# iDAC2.net
KiCad netlist of a schematic drawn in Altium Designer
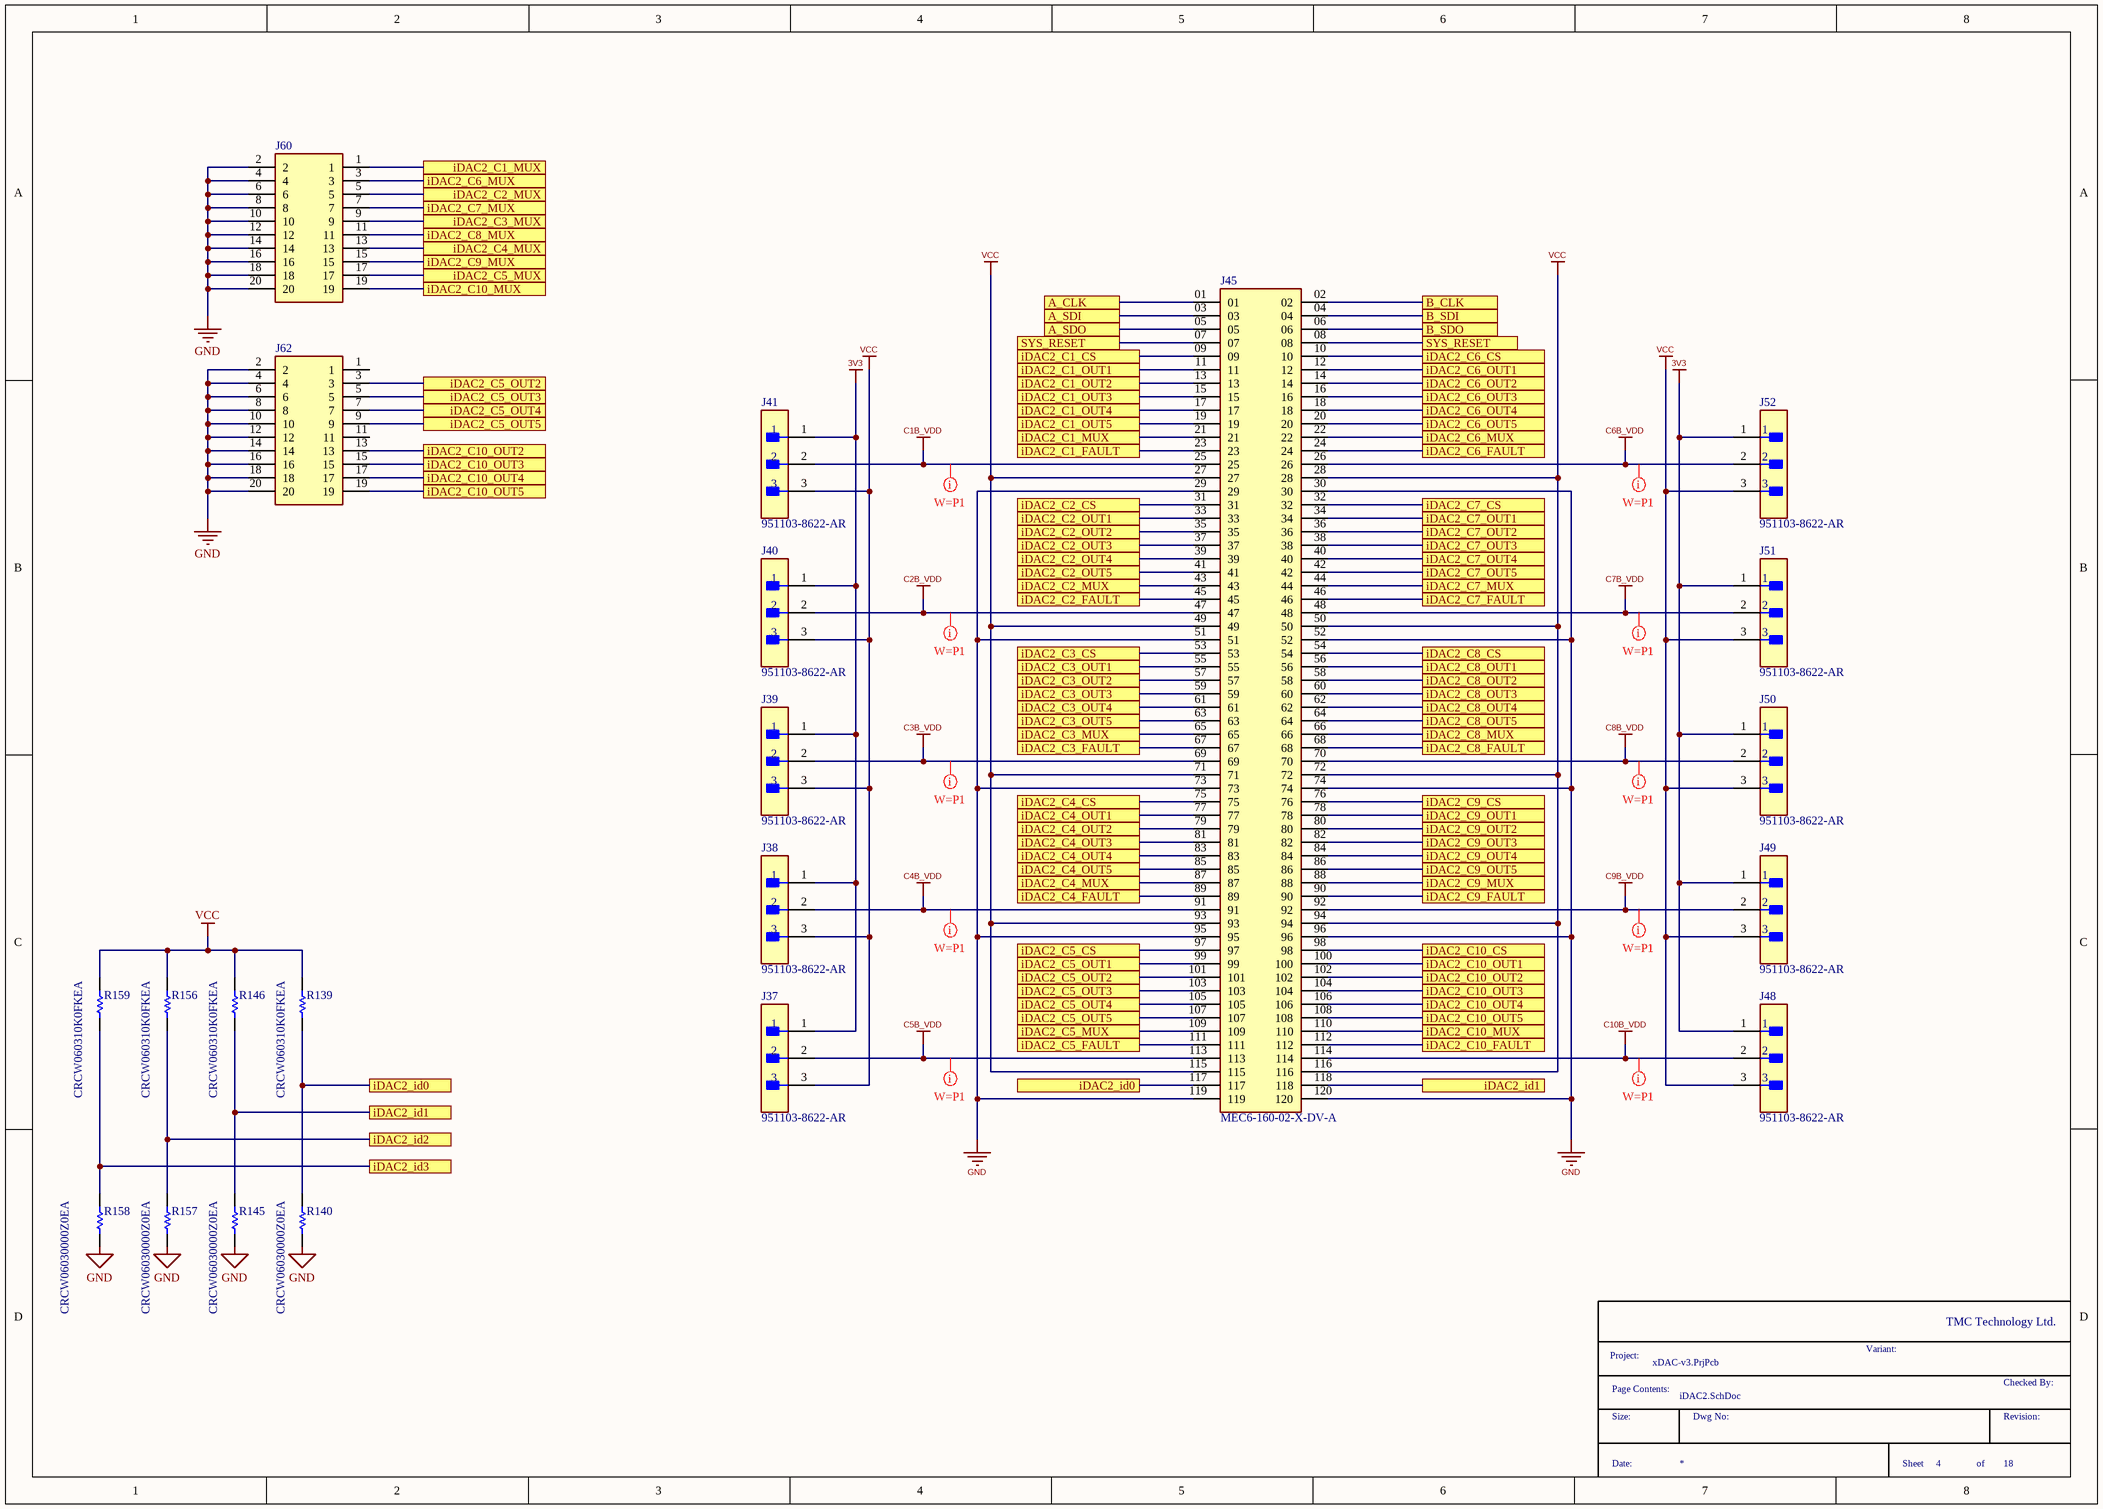
[diagram p0: iDAC2.SchDoc]

(export (version "E")
  (design (tool "Eeschema 10.0.6"))
  (components
    (comp (ref "J37")
      (value "951103-8622-AR")
      (footprint "FP-951103-8622-AR-MFG")
      (description "CONN HEADER VERT 3POS 2MM")
      (fields
        (field (name "OCTOPART") "https://octopart.com/951103-8622-ar-3m-14400669")
        (field (name "MANUFACTURER") "3M")
      )
      (libsource (lib "xDAC_Carrier") (part "CMP-05379-000003-1"))
    )
    (comp (ref "J38")
      (value "951103-8622-AR")
      (footprint "FP-951103-8622-AR-MFG")
      (description "CONN HEADER VERT 3POS 2MM")
      (fields
        (field (name "OCTOPART") "https://octopart.com/951103-8622-ar-3m-14400669")
        (field (name "MANUFACTURER") "3M")
      )
      (libsource (lib "xDAC_Carrier") (part "CMP-05379-000003-1"))
    )
    (comp (ref "J39")
      (value "951103-8622-AR")
      (footprint "FP-951103-8622-AR-MFG")
      (description "CONN HEADER VERT 3POS 2MM")
      (fields
        (field (name "OCTOPART") "https://octopart.com/951103-8622-ar-3m-14400669")
        (field (name "MANUFACTURER") "3M")
      )
      (libsource (lib "xDAC_Carrier") (part "CMP-05379-000003-1"))
    )
    (comp (ref "J40")
      (value "951103-8622-AR")
      (footprint "FP-951103-8622-AR-MFG")
      (description "CONN HEADER VERT 3POS 2MM")
      (fields
        (field (name "OCTOPART") "https://octopart.com/951103-8622-ar-3m-14400669")
        (field (name "MANUFACTURER") "3M")
      )
      (libsource (lib "xDAC_Carrier") (part "CMP-05379-000003-1"))
    )
    (comp (ref "J41")
      (value "951103-8622-AR")
      (footprint "FP-951103-8622-AR-MFG")
      (description "CONN HEADER VERT 3POS 2MM")
      (fields
        (field (name "OCTOPART") "https://octopart.com/951103-8622-ar-3m-14400669")
        (field (name "MANUFACTURER") "3M")
      )
      (libsource (lib "xDAC_Carrier") (part "CMP-05379-000003-1"))
    )
    (comp (ref "J45")
      (value "MEC6-160-02-X-DV-A")
      (footprint "SAMTEC_MEC6-160-02-X-DV-A")
      (fields (field (name "MF") "Samtec Inc."))
      (libsource (lib "xDAC_Carrier") (part "MEC6-160-02-X-DV-A"))
    )
    (comp (ref "J48")
      (value "951103-8622-AR")
      (footprint "FP-951103-8622-AR-MFG")
      (description "CONN HEADER VERT 3POS 2MM")
      (fields
        (field (name "OCTOPART") "https://octopart.com/951103-8622-ar-3m-14400669")
        (field (name "MANUFACTURER") "3M")
      )
      (libsource (lib "") (part "CMP-05379-000003-1_1"))
    )
    (comp (ref "J49")
      (value "951103-8622-AR")
      (footprint "FP-951103-8622-AR-MFG")
      (description "CONN HEADER VERT 3POS 2MM")
      (fields
        (field (name "OCTOPART") "https://octopart.com/951103-8622-ar-3m-14400669")
        (field (name "MANUFACTURER") "3M")
      )
      (libsource (lib "") (part "CMP-05379-000003-1_1"))
    )
    (comp (ref "J50")
      (value "951103-8622-AR")
      (footprint "FP-951103-8622-AR-MFG")
      (description "CONN HEADER VERT 3POS 2MM")
      (fields
        (field (name "OCTOPART") "https://octopart.com/951103-8622-ar-3m-14400669")
        (field (name "MANUFACTURER") "3M")
      )
      (libsource (lib "") (part "CMP-05379-000003-1_1"))
    )
    (comp (ref "J51")
      (value "951103-8622-AR")
      (footprint "FP-951103-8622-AR-MFG")
      (description "CONN HEADER VERT 3POS 2MM")
      (fields
        (field (name "OCTOPART") "https://octopart.com/951103-8622-ar-3m-14400669")
        (field (name "MANUFACTURER") "3M")
      )
      (libsource (lib "") (part "CMP-05379-000003-1_1"))
    )
    (comp (ref "J52")
      (value "951103-8622-AR")
      (footprint "FP-951103-8622-AR-MFG")
      (description "CONN HEADER VERT 3POS 2MM")
      (fields
        (field (name "OCTOPART") "https://octopart.com/951103-8622-ar-3m-14400669")
        (field (name "MANUFACTURER") "3M")
      )
      (libsource (lib "") (part "CMP-05379-000003-1_1"))
    )
    (comp (ref "J60")
      (value "~")
      (footprint "HDRV20W40P127_2X10_1270X340X550P")
      (description "Connector")
      (fields (field (name "MANUFACTURER_PART_NUMBER") "20021111-00020T4LF"))
      (libsource (lib "xDAC_Carrier") (part "20021111-00020T4LF"))
    )
    (comp (ref "J62")
      (value "~")
      (footprint "HDRV20W40P127_2X10_1270X340X550P")
      (description "Connector")
      (fields (field (name "MANUFACTURER_PART_NUMBER") "20021111-00020T4LF"))
      (libsource (lib "xDAC_Carrier") (part "20021111-00020T4LF"))
    )
    (comp (ref "R139")
      (value "CRCW060310K0FKEA")
      (footprint "RESC1609X50X30NL8T20")
      (description "Chip Resistor, 10 KOhm, +/- 1%, 100 mW, -55 to 155 degC, 0603 (1608 Metric), RoHS, Tape and Reel")
      (fields (field (name "MANUFACTURER") "Vishay Semiconductor"))
      (libsource (lib "Altium Content Vault") (part "RES-2"))
    )
    (comp (ref "R140")
      (value "CRCW06030000Z0EA")
      (footprint "RESC1609X50X30NL8T20")
      (description "Chip Resistor, 0 Ohm, Jumper, 100 mW, -55 to 155 degC, 0603 (1608 Metric), RoHS, Tape and Reel")
      (fields (field (name "MANUFACTURER") "Vishay Semiconductor"))
      (libsource (lib "Altium Content Vault") (part "RES-2"))
    )
    (comp (ref "R145")
      (value "CRCW06030000Z0EA")
      (footprint "RESC1609X50X30NL8T20")
      (description "Chip Resistor, 0 Ohm, Jumper, 100 mW, -55 to 155 degC, 0603 (1608 Metric), RoHS, Tape and Reel")
      (fields (field (name "MANUFACTURER") "Vishay Semiconductor"))
      (libsource (lib "Altium Content Vault") (part "RES-2"))
    )
    (comp (ref "R146")
      (value "CRCW060310K0FKEA")
      (footprint "RESC1609X50X30NL8T20")
      (description "Chip Resistor, 10 KOhm, +/- 1%, 100 mW, -55 to 155 degC, 0603 (1608 Metric), RoHS, Tape and Reel")
      (fields (field (name "MANUFACTURER") "Vishay Semiconductor"))
      (libsource (lib "Altium Content Vault") (part "RES-2"))
    )
    (comp (ref "R156")
      (value "CRCW060310K0FKEA")
      (footprint "RESC1609X50X30NL8T20")
      (description "Chip Resistor, 10 KOhm, +/- 1%, 100 mW, -55 to 155 degC, 0603 (1608 Metric), RoHS, Tape and Reel")
      (fields (field (name "MANUFACTURER") "Vishay Semiconductor"))
      (libsource (lib "Altium Content Vault") (part "RES-2"))
    )
    (comp (ref "R157")
      (value "CRCW06030000Z0EA")
      (footprint "RESC1609X50X30NL8T20")
      (description "Chip Resistor, 0 Ohm, Jumper, 100 mW, -55 to 155 degC, 0603 (1608 Metric), RoHS, Tape and Reel")
      (fields (field (name "MANUFACTURER") "Vishay Semiconductor"))
      (libsource (lib "Altium Content Vault") (part "RES-2"))
    )
    (comp (ref "R158")
      (value "CRCW06030000Z0EA")
      (footprint "RESC1609X50X30NL8T20")
      (description "Chip Resistor, 0 Ohm, Jumper, 100 mW, -55 to 155 degC, 0603 (1608 Metric), RoHS, Tape and Reel")
      (fields (field (name "MANUFACTURER") "Vishay Semiconductor"))
      (libsource (lib "Altium Content Vault") (part "RES-2"))
    )
    (comp (ref "R159")
      (value "CRCW060310K0FKEA")
      (footprint "RESC1609X50X30NL8T20")
      (description "Chip Resistor, 10 KOhm, +/- 1%, 100 mW, -55 to 155 degC, 0603 (1608 Metric), RoHS, Tape and Reel")
      (fields (field (name "MANUFACTURER") "Vishay Semiconductor"))
      (libsource (lib "Altium Content Vault") (part "RES-2"))
    )
  )
  (nets
    (net (code "1") (name "/A_CLK") (class "Default")
      (node (ref "J45") (pin "01") (pinfunction "01_01") (pintype "passive"))
    )
    (net (code "2") (name "/A_SDI") (class "Default")
      (node (ref "J45") (pin "03") (pinfunction "03_03") (pintype "passive"))
    )
    (net (code "3") (name "/A_SDO") (class "Default")
      (node (ref "J45") (pin "05") (pinfunction "05_05") (pintype "passive"))
    )
    (net (code "4") (name "/B_CLK") (class "Default")
      (node (ref "J45") (pin "02") (pinfunction "02_02") (pintype "passive"))
    )
    (net (code "5") (name "/B_SDI") (class "Default")
      (node (ref "J45") (pin "04") (pinfunction "04_04") (pintype "passive"))
    )
    (net (code "6") (name "/B_SDO") (class "Default")
      (node (ref "J45") (pin "06") (pinfunction "06_06") (pintype "passive"))
    )
    (net (code "7") (name "/SYS_RESET") (class "Default")
      (node (ref "J45") (pin "07") (pinfunction "07_07") (pintype "passive"))
      (node (ref "J45") (pin "08") (pinfunction "08_08") (pintype "passive"))
    )
    (net (code "8") (name "/iDAC2_C1_CS") (class "Default")
      (node (ref "J45") (pin "09") (pinfunction "09_09") (pintype "passive"))
    )
    (net (code "9") (name "/iDAC2_C1_FAULT") (class "Default")
      (node (ref "J45") (pin "23") (pinfunction "23_23") (pintype "passive"))
    )
    (net (code "10") (name "/iDAC2_C1_MUX") (class "Default")
      (node (ref "J45") (pin "21") (pinfunction "21_21") (pintype "passive"))
      (node (ref "J60") (pin "1") (pinfunction "1_1") (pintype "passive"))
    )
    (net (code "11") (name "/iDAC2_C1_OUT1") (class "Default")
      (node (ref "J45") (pin "11") (pinfunction "11_11") (pintype "passive"))
    )
    (net (code "12") (name "/iDAC2_C1_OUT2") (class "Default")
      (node (ref "J45") (pin "13") (pinfunction "13_13") (pintype "passive"))
    )
    (net (code "13") (name "/iDAC2_C1_OUT3") (class "Default")
      (node (ref "J45") (pin "15") (pinfunction "15_15") (pintype "passive"))
    )
    (net (code "14") (name "/iDAC2_C1_OUT4") (class "Default")
      (node (ref "J45") (pin "17") (pinfunction "17_17") (pintype "passive"))
    )
    (net (code "15") (name "/iDAC2_C1_OUT5") (class "Default")
      (node (ref "J45") (pin "19") (pinfunction "19_19") (pintype "passive"))
    )
    (net (code "16") (name "/iDAC2_C2_CS") (class "Default")
      (node (ref "J45") (pin "31") (pinfunction "31_31") (pintype "passive"))
    )
    (net (code "17") (name "/iDAC2_C2_FAULT") (class "Default")
      (node (ref "J45") (pin "45") (pinfunction "45_45") (pintype "passive"))
    )
    (net (code "18") (name "/iDAC2_C2_MUX") (class "Default")
      (node (ref "J45") (pin "43") (pinfunction "43_43") (pintype "passive"))
      (node (ref "J60") (pin "5") (pinfunction "5_5") (pintype "passive"))
    )
    (net (code "19") (name "/iDAC2_C2_OUT1") (class "Default")
      (node (ref "J45") (pin "33") (pinfunction "33_33") (pintype "passive"))
    )
    (net (code "20") (name "/iDAC2_C2_OUT2") (class "Default")
      (node (ref "J45") (pin "35") (pinfunction "35_35") (pintype "passive"))
    )
    (net (code "21") (name "/iDAC2_C2_OUT3") (class "Default")
      (node (ref "J45") (pin "37") (pinfunction "37_37") (pintype "passive"))
    )
    (net (code "22") (name "/iDAC2_C2_OUT4") (class "Default")
      (node (ref "J45") (pin "39") (pinfunction "39_39") (pintype "passive"))
    )
    (net (code "23") (name "/iDAC2_C2_OUT5") (class "Default")
      (node (ref "J45") (pin "41") (pinfunction "41_41") (pintype "passive"))
    )
    (net (code "24") (name "/iDAC2_C3_CS") (class "Default")
      (node (ref "J45") (pin "53") (pinfunction "53_53") (pintype "passive"))
    )
    (net (code "25") (name "/iDAC2_C3_FAULT") (class "Default")
      (node (ref "J45") (pin "67") (pinfunction "67_67") (pintype "passive"))
    )
    (net (code "26") (name "/iDAC2_C3_MUX") (class "Default")
      (node (ref "J45") (pin "65") (pinfunction "65_65") (pintype "passive"))
      (node (ref "J60") (pin "9") (pinfunction "9_9") (pintype "passive"))
    )
    (net (code "27") (name "/iDAC2_C3_OUT1") (class "Default")
      (node (ref "J45") (pin "55") (pinfunction "55_55") (pintype "passive"))
    )
    (net (code "28") (name "/iDAC2_C3_OUT2") (class "Default")
      (node (ref "J45") (pin "57") (pinfunction "57_57") (pintype "passive"))
    )
    (net (code "29") (name "/iDAC2_C3_OUT3") (class "Default")
      (node (ref "J45") (pin "59") (pinfunction "59_59") (pintype "passive"))
    )
    (net (code "30") (name "/iDAC2_C3_OUT4") (class "Default")
      (node (ref "J45") (pin "61") (pinfunction "61_61") (pintype "passive"))
    )
    (net (code "31") (name "/iDAC2_C3_OUT5") (class "Default")
      (node (ref "J45") (pin "63") (pinfunction "63_63") (pintype "passive"))
    )
    (net (code "32") (name "/iDAC2_C4_CS") (class "Default")
      (node (ref "J45") (pin "75") (pinfunction "75_75") (pintype "passive"))
    )
    (net (code "33") (name "/iDAC2_C4_FAULT") (class "Default")
      (node (ref "J45") (pin "89") (pinfunction "89_89") (pintype "passive"))
    )
    (net (code "34") (name "/iDAC2_C4_MUX") (class "Default")
      (node (ref "J45") (pin "87") (pinfunction "87_87") (pintype "passive"))
      (node (ref "J60") (pin "13") (pinfunction "13_13") (pintype "passive"))
    )
    (net (code "35") (name "/iDAC2_C4_OUT1") (class "Default")
      (node (ref "J45") (pin "77") (pinfunction "77_77") (pintype "passive"))
    )
    (net (code "36") (name "/iDAC2_C4_OUT2") (class "Default")
      (node (ref "J45") (pin "79") (pinfunction "79_79") (pintype "passive"))
    )
    (net (code "37") (name "/iDAC2_C4_OUT3") (class "Default")
      (node (ref "J45") (pin "81") (pinfunction "81_81") (pintype "passive"))
    )
    (net (code "38") (name "/iDAC2_C4_OUT4") (class "Default")
      (node (ref "J45") (pin "83") (pinfunction "83_83") (pintype "passive"))
    )
    (net (code "39") (name "/iDAC2_C4_OUT5") (class "Default")
      (node (ref "J45") (pin "85") (pinfunction "85_85") (pintype "passive"))
    )
    (net (code "40") (name "/iDAC2_C5_CS") (class "Default")
      (node (ref "J45") (pin "97") (pinfunction "97_97") (pintype "passive"))
    )
    (net (code "41") (name "/iDAC2_C5_FAULT") (class "Default")
      (node (ref "J45") (pin "111") (pinfunction "111_111") (pintype "passive"))
    )
    (net (code "42") (name "/iDAC2_C5_MUX") (class "Default")
      (node (ref "J45") (pin "109") (pinfunction "109_109") (pintype "passive"))
      (node (ref "J60") (pin "17") (pinfunction "17_17") (pintype "passive"))
    )
    (net (code "43") (name "/iDAC2_C5_OUT1") (class "Default")
      (node (ref "J45") (pin "99") (pinfunction "99_99") (pintype "passive"))
    )
    (net (code "44") (name "/iDAC2_C5_OUT2") (class "Default")
      (node (ref "J45") (pin "101") (pinfunction "101_101") (pintype "passive"))
      (node (ref "J62") (pin "3") (pinfunction "3_3") (pintype "passive"))
    )
    (net (code "45") (name "/iDAC2_C5_OUT3") (class "Default")
      (node (ref "J45") (pin "103") (pinfunction "103_103") (pintype "passive"))
      (node (ref "J62") (pin "5") (pinfunction "5_5") (pintype "passive"))
    )
    (net (code "46") (name "/iDAC2_C5_OUT4") (class "Default")
      (node (ref "J45") (pin "105") (pinfunction "105_105") (pintype "passive"))
      (node (ref "J62") (pin "7") (pinfunction "7_7") (pintype "passive"))
    )
    (net (code "47") (name "/iDAC2_C5_OUT5") (class "Default")
      (node (ref "J45") (pin "107") (pinfunction "107_107") (pintype "passive"))
      (node (ref "J62") (pin "9") (pinfunction "9_9") (pintype "passive"))
    )
    (net (code "48") (name "/iDAC2_C6_CS") (class "Default")
      (node (ref "J45") (pin "10") (pinfunction "10_10") (pintype "passive"))
    )
    (net (code "49") (name "/iDAC2_C6_FAULT") (class "Default")
      (node (ref "J45") (pin "24") (pinfunction "24_24") (pintype "passive"))
    )
    (net (code "50") (name "/iDAC2_C6_MUX") (class "Default")
      (node (ref "J45") (pin "22") (pinfunction "22_22") (pintype "passive"))
      (node (ref "J60") (pin "3") (pinfunction "3_3") (pintype "passive"))
    )
    (net (code "51") (name "/iDAC2_C6_OUT1") (class "Default")
      (node (ref "J45") (pin "12") (pinfunction "12_12") (pintype "passive"))
    )
    (net (code "52") (name "/iDAC2_C6_OUT2") (class "Default")
      (node (ref "J45") (pin "14") (pinfunction "14_14") (pintype "passive"))
    )
    (net (code "53") (name "/iDAC2_C6_OUT3") (class "Default")
      (node (ref "J45") (pin "16") (pinfunction "16_16") (pintype "passive"))
    )
    (net (code "54") (name "/iDAC2_C6_OUT4") (class "Default")
      (node (ref "J45") (pin "18") (pinfunction "18_18") (pintype "passive"))
    )
    (net (code "55") (name "/iDAC2_C6_OUT5") (class "Default")
      (node (ref "J45") (pin "20") (pinfunction "20_20") (pintype "passive"))
    )
    (net (code "56") (name "/iDAC2_C7_CS") (class "Default")
      (node (ref "J45") (pin "32") (pinfunction "32_32") (pintype "passive"))
    )
    (net (code "57") (name "/iDAC2_C7_FAULT") (class "Default")
      (node (ref "J45") (pin "46") (pinfunction "46_46") (pintype "passive"))
    )
    (net (code "58") (name "/iDAC2_C7_MUX") (class "Default")
      (node (ref "J45") (pin "44") (pinfunction "44_44") (pintype "passive"))
      (node (ref "J60") (pin "7") (pinfunction "7_7") (pintype "passive"))
    )
    (net (code "59") (name "/iDAC2_C7_OUT1") (class "Default")
      (node (ref "J45") (pin "34") (pinfunction "34_34") (pintype "passive"))
    )
    (net (code "60") (name "/iDAC2_C7_OUT2") (class "Default")
      (node (ref "J45") (pin "36") (pinfunction "36_36") (pintype "passive"))
    )
    (net (code "61") (name "/iDAC2_C7_OUT3") (class "Default")
      (node (ref "J45") (pin "38") (pinfunction "38_38") (pintype "passive"))
    )
    (net (code "62") (name "/iDAC2_C7_OUT4") (class "Default")
      (node (ref "J45") (pin "40") (pinfunction "40_40") (pintype "passive"))
    )
    (net (code "63") (name "/iDAC2_C7_OUT5") (class "Default")
      (node (ref "J45") (pin "42") (pinfunction "42_42") (pintype "passive"))
    )
    (net (code "64") (name "/iDAC2_C8_CS") (class "Default")
      (node (ref "J45") (pin "54") (pinfunction "54_54") (pintype "passive"))
    )
    (net (code "65") (name "/iDAC2_C8_FAULT") (class "Default")
      (node (ref "J45") (pin "68") (pinfunction "68_68") (pintype "passive"))
    )
    (net (code "66") (name "/iDAC2_C8_MUX") (class "Default")
      (node (ref "J45") (pin "66") (pinfunction "66_66") (pintype "passive"))
      (node (ref "J60") (pin "11") (pinfunction "11_11") (pintype "passive"))
    )
    (net (code "67") (name "/iDAC2_C8_OUT1") (class "Default")
      (node (ref "J45") (pin "56") (pinfunction "56_56") (pintype "passive"))
    )
    (net (code "68") (name "/iDAC2_C8_OUT2") (class "Default")
      (node (ref "J45") (pin "58") (pinfunction "58_58") (pintype "passive"))
    )
    (net (code "69") (name "/iDAC2_C8_OUT3") (class "Default")
      (node (ref "J45") (pin "60") (pinfunction "60_60") (pintype "passive"))
    )
    (net (code "70") (name "/iDAC2_C8_OUT4") (class "Default")
      (node (ref "J45") (pin "62") (pinfunction "62_62") (pintype "passive"))
    )
    (net (code "71") (name "/iDAC2_C8_OUT5") (class "Default")
      (node (ref "J45") (pin "64") (pinfunction "64_64") (pintype "passive"))
    )
    (net (code "72") (name "/iDAC2_C9_CS") (class "Default")
      (node (ref "J45") (pin "76") (pinfunction "76_76") (pintype "passive"))
    )
    (net (code "73") (name "/iDAC2_C9_FAULT") (class "Default")
      (node (ref "J45") (pin "90") (pinfunction "90_90") (pintype "passive"))
    )
    (net (code "74") (name "/iDAC2_C9_MUX") (class "Default")
      (node (ref "J45") (pin "88") (pinfunction "88_88") (pintype "passive"))
      (node (ref "J60") (pin "15") (pinfunction "15_15") (pintype "passive"))
    )
    (net (code "75") (name "/iDAC2_C9_OUT1") (class "Default")
      (node (ref "J45") (pin "78") (pinfunction "78_78") (pintype "passive"))
    )
    (net (code "76") (name "/iDAC2_C9_OUT2") (class "Default")
      (node (ref "J45") (pin "80") (pinfunction "80_80") (pintype "passive"))
    )
    (net (code "77") (name "/iDAC2_C9_OUT3") (class "Default")
      (node (ref "J45") (pin "82") (pinfunction "82_82") (pintype "passive"))
    )
    (net (code "78") (name "/iDAC2_C9_OUT4") (class "Default")
      (node (ref "J45") (pin "84") (pinfunction "84_84") (pintype "passive"))
    )
    (net (code "79") (name "/iDAC2_C9_OUT5") (class "Default")
      (node (ref "J45") (pin "86") (pinfunction "86_86") (pintype "passive"))
    )
    (net (code "80") (name "/iDAC2_C10_CS") (class "Default")
      (node (ref "J45") (pin "98") (pinfunction "98_98") (pintype "passive"))
    )
    (net (code "81") (name "/iDAC2_C10_FAULT") (class "Default")
      (node (ref "J45") (pin "112") (pinfunction "112_112") (pintype "passive"))
    )
    (net (code "82") (name "/iDAC2_C10_MUX") (class "Default")
      (node (ref "J45") (pin "110") (pinfunction "110_110") (pintype "passive"))
      (node (ref "J60") (pin "19") (pinfunction "19_19") (pintype "passive"))
    )
    (net (code "83") (name "/iDAC2_C10_OUT1") (class "Default")
      (node (ref "J45") (pin "100") (pinfunction "100_100") (pintype "passive"))
    )
    (net (code "84") (name "/iDAC2_C10_OUT2") (class "Default")
      (node (ref "J45") (pin "102") (pinfunction "102_102") (pintype "passive"))
      (node (ref "J62") (pin "13") (pinfunction "13_13") (pintype "passive"))
    )
    (net (code "85") (name "/iDAC2_C10_OUT3") (class "Default")
      (node (ref "J45") (pin "104") (pinfunction "104_104") (pintype "passive"))
      (node (ref "J62") (pin "15") (pinfunction "15_15") (pintype "passive"))
    )
    (net (code "86") (name "/iDAC2_C10_OUT4") (class "Default")
      (node (ref "J45") (pin "106") (pinfunction "106_106") (pintype "passive"))
      (node (ref "J62") (pin "17") (pinfunction "17_17") (pintype "passive"))
    )
    (net (code "87") (name "/iDAC2_C10_OUT5") (class "Default")
      (node (ref "J45") (pin "108") (pinfunction "108_108") (pintype "passive"))
      (node (ref "J62") (pin "19") (pinfunction "19_19") (pintype "passive"))
    )
    (net (code "88") (name "/iDAC2_id0") (class "Default")
      (node (ref "J45") (pin "117") (pinfunction "117_117") (pintype "passive"))
      (node (ref "R139") (pin "1") (pinfunction "1_1") (pintype "passive"))
      (node (ref "R140") (pin "2") (pinfunction "2_2") (pintype "passive"))
    )
    (net (code "89") (name "/iDAC2_id1") (class "Default")
      (node (ref "J45") (pin "118") (pinfunction "118_118") (pintype "passive"))
      (node (ref "R145") (pin "2") (pinfunction "2_2") (pintype "passive"))
      (node (ref "R146") (pin "1") (pinfunction "1_1") (pintype "passive"))
    )
    (net (code "90") (name "/iDAC2_id2") (class "Default")
      (node (ref "R156") (pin "1") (pinfunction "1_1") (pintype "passive"))
      (node (ref "R157") (pin "2") (pinfunction "2_2") (pintype "passive"))
    )
    (net (code "91") (name "/iDAC2_id3") (class "Default")
      (node (ref "R158") (pin "2") (pinfunction "2_2") (pintype "passive"))
      (node (ref "R159") (pin "1") (pinfunction "1_1") (pintype "passive"))
    )
    (net (code "92") (name "3V3") (class "Default")
      (node (ref "J37") (pin "1") (pinfunction "1_1") (pintype "passive"))
      (node (ref "J38") (pin "1") (pinfunction "1_1") (pintype "passive"))
      (node (ref "J39") (pin "1") (pinfunction "1_1") (pintype "passive"))
      (node (ref "J40") (pin "1") (pinfunction "1_1") (pintype "passive"))
      (node (ref "J41") (pin "1") (pinfunction "1_1") (pintype "passive"))
      (node (ref "J48") (pin "1") (pinfunction "1_1") (pintype "passive"))
      (node (ref "J49") (pin "1") (pinfunction "1_1") (pintype "passive"))
      (node (ref "J50") (pin "1") (pinfunction "1_1") (pintype "passive"))
      (node (ref "J51") (pin "1") (pinfunction "1_1") (pintype "passive"))
      (node (ref "J52") (pin "1") (pinfunction "1_1") (pintype "passive"))
    )
    (net (code "93") (name "C1B_VDD") (class "Default")
      (node (ref "J41") (pin "2") (pinfunction "2_2") (pintype "passive"))
      (node (ref "J45") (pin "25") (pinfunction "25_25") (pintype "passive"))
    )
    (net (code "94") (name "C2B_VDD") (class "Default")
      (node (ref "J40") (pin "2") (pinfunction "2_2") (pintype "passive"))
      (node (ref "J45") (pin "47") (pinfunction "47_47") (pintype "passive"))
    )
    (net (code "95") (name "C3B_VDD") (class "Default")
      (node (ref "J39") (pin "2") (pinfunction "2_2") (pintype "passive"))
      (node (ref "J45") (pin "69") (pinfunction "69_69") (pintype "passive"))
    )
    (net (code "96") (name "C4B_VDD") (class "Default")
      (node (ref "J38") (pin "2") (pinfunction "2_2") (pintype "passive"))
      (node (ref "J45") (pin "91") (pinfunction "91_91") (pintype "passive"))
    )
    (net (code "97") (name "C5B_VDD") (class "Default")
      (node (ref "J37") (pin "2") (pinfunction "2_2") (pintype "passive"))
      (node (ref "J45") (pin "113") (pinfunction "113_113") (pintype "passive"))
    )
    (net (code "98") (name "C6B_VDD") (class "Default")
      (node (ref "J45") (pin "26") (pinfunction "26_26") (pintype "passive"))
      (node (ref "J52") (pin "2") (pinfunction "2_2") (pintype "passive"))
    )
    (net (code "99") (name "C7B_VDD") (class "Default")
      (node (ref "J45") (pin "48") (pinfunction "48_48") (pintype "passive"))
      (node (ref "J51") (pin "2") (pinfunction "2_2") (pintype "passive"))
    )
    (net (code "100") (name "C8B_VDD") (class "Default")
      (node (ref "J45") (pin "70") (pinfunction "70_70") (pintype "passive"))
      (node (ref "J50") (pin "2") (pinfunction "2_2") (pintype "passive"))
    )
    (net (code "101") (name "C9B_VDD") (class "Default")
      (node (ref "J45") (pin "92") (pinfunction "92_92") (pintype "passive"))
      (node (ref "J49") (pin "2") (pinfunction "2_2") (pintype "passive"))
    )
    (net (code "102") (name "C10B_VDD") (class "Default")
      (node (ref "J45") (pin "114") (pinfunction "114_114") (pintype "passive"))
      (node (ref "J48") (pin "2") (pinfunction "2_2") (pintype "passive"))
    )
    (net (code "103") (name "GND") (class "Default")
      (node (ref "J45") (pin "119") (pinfunction "119_119") (pintype "passive"))
      (node (ref "J45") (pin "120") (pinfunction "120_120") (pintype "passive"))
      (node (ref "J45") (pin "29") (pinfunction "29_29") (pintype "passive"))
      (node (ref "J45") (pin "30") (pinfunction "30_30") (pintype "passive"))
      (node (ref "J45") (pin "51") (pinfunction "51_51") (pintype "passive"))
      (node (ref "J45") (pin "52") (pinfunction "52_52") (pintype "passive"))
      (node (ref "J45") (pin "73") (pinfunction "73_73") (pintype "passive"))
      (node (ref "J45") (pin "74") (pinfunction "74_74") (pintype "passive"))
      (node (ref "J45") (pin "95") (pinfunction "95_95") (pintype "passive"))
      (node (ref "J45") (pin "96") (pinfunction "96_96") (pintype "passive"))
      (node (ref "J60") (pin "10") (pinfunction "10_10") (pintype "passive"))
      (node (ref "J60") (pin "12") (pinfunction "12_12") (pintype "passive"))
      (node (ref "J60") (pin "14") (pinfunction "14_14") (pintype "passive"))
      (node (ref "J60") (pin "16") (pinfunction "16_16") (pintype "passive"))
      (node (ref "J60") (pin "18") (pinfunction "18_18") (pintype "passive"))
      (node (ref "J60") (pin "2") (pinfunction "2_2") (pintype "passive"))
      (node (ref "J60") (pin "20") (pinfunction "20_20") (pintype "passive"))
      (node (ref "J60") (pin "4") (pinfunction "4_4") (pintype "passive"))
      (node (ref "J60") (pin "6") (pinfunction "6_6") (pintype "passive"))
      (node (ref "J60") (pin "8") (pinfunction "8_8") (pintype "passive"))
      (node (ref "J62") (pin "10") (pinfunction "10_10") (pintype "passive"))
      (node (ref "J62") (pin "12") (pinfunction "12_12") (pintype "passive"))
      (node (ref "J62") (pin "14") (pinfunction "14_14") (pintype "passive"))
      (node (ref "J62") (pin "16") (pinfunction "16_16") (pintype "passive"))
      (node (ref "J62") (pin "18") (pinfunction "18_18") (pintype "passive"))
      (node (ref "J62") (pin "2") (pinfunction "2_2") (pintype "passive"))
      (node (ref "J62") (pin "20") (pinfunction "20_20") (pintype "passive"))
      (node (ref "J62") (pin "4") (pinfunction "4_4") (pintype "passive"))
      (node (ref "J62") (pin "6") (pinfunction "6_6") (pintype "passive"))
      (node (ref "J62") (pin "8") (pinfunction "8_8") (pintype "passive"))
      (node (ref "R140") (pin "1") (pinfunction "1_1") (pintype "passive"))
      (node (ref "R145") (pin "1") (pinfunction "1_1") (pintype "passive"))
      (node (ref "R157") (pin "1") (pinfunction "1_1") (pintype "passive"))
      (node (ref "R158") (pin "1") (pinfunction "1_1") (pintype "passive"))
    )
    (net (code "104") (name "VCC") (class "Default")
      (node (ref "J37") (pin "3") (pinfunction "3_3") (pintype "passive"))
      (node (ref "J38") (pin "3") (pinfunction "3_3") (pintype "passive"))
      (node (ref "J39") (pin "3") (pinfunction "3_3") (pintype "passive"))
      (node (ref "J40") (pin "3") (pinfunction "3_3") (pintype "passive"))
      (node (ref "J41") (pin "3") (pinfunction "3_3") (pintype "passive"))
      (node (ref "J45") (pin "115") (pinfunction "115_115") (pintype "passive"))
      (node (ref "J45") (pin "116") (pinfunction "116_116") (pintype "passive"))
      (node (ref "J45") (pin "27") (pinfunction "27_27") (pintype "passive"))
      (node (ref "J45") (pin "28") (pinfunction "28_28") (pintype "passive"))
      (node (ref "J45") (pin "49") (pinfunction "49_49") (pintype "passive"))
      (node (ref "J45") (pin "50") (pinfunction "50_50") (pintype "passive"))
      (node (ref "J45") (pin "71") (pinfunction "71_71") (pintype "passive"))
      (node (ref "J45") (pin "72") (pinfunction "72_72") (pintype "passive"))
      (node (ref "J45") (pin "93") (pinfunction "93_93") (pintype "passive"))
      (node (ref "J45") (pin "94") (pinfunction "94_94") (pintype "passive"))
      (node (ref "J48") (pin "3") (pinfunction "3_3") (pintype "passive"))
      (node (ref "J49") (pin "3") (pinfunction "3_3") (pintype "passive"))
      (node (ref "J50") (pin "3") (pinfunction "3_3") (pintype "passive"))
      (node (ref "J51") (pin "3") (pinfunction "3_3") (pintype "passive"))
      (node (ref "J52") (pin "3") (pinfunction "3_3") (pintype "passive"))
      (node (ref "R139") (pin "2") (pinfunction "2_2") (pintype "passive"))
      (node (ref "R146") (pin "2") (pinfunction "2_2") (pintype "passive"))
      (node (ref "R156") (pin "2") (pinfunction "2_2") (pintype "passive"))
      (node (ref "R159") (pin "2") (pinfunction "2_2") (pintype "passive"))
    )
    (net (code "105") (name "unconnected-(J62-Pad1)") (class "Default")
      (node (ref "J62") (pin "1") (pinfunction "1_1") (pintype "passive"))
    )
    (net (code "106") (name "unconnected-(J62-Pad11)") (class "Default")
      (node (ref "J62") (pin "11") (pinfunction "11_11") (pintype "passive"))
    )
  )
)
